# primary_LTC.net
KiCad netlist of a schematic drawn in Altium Designer
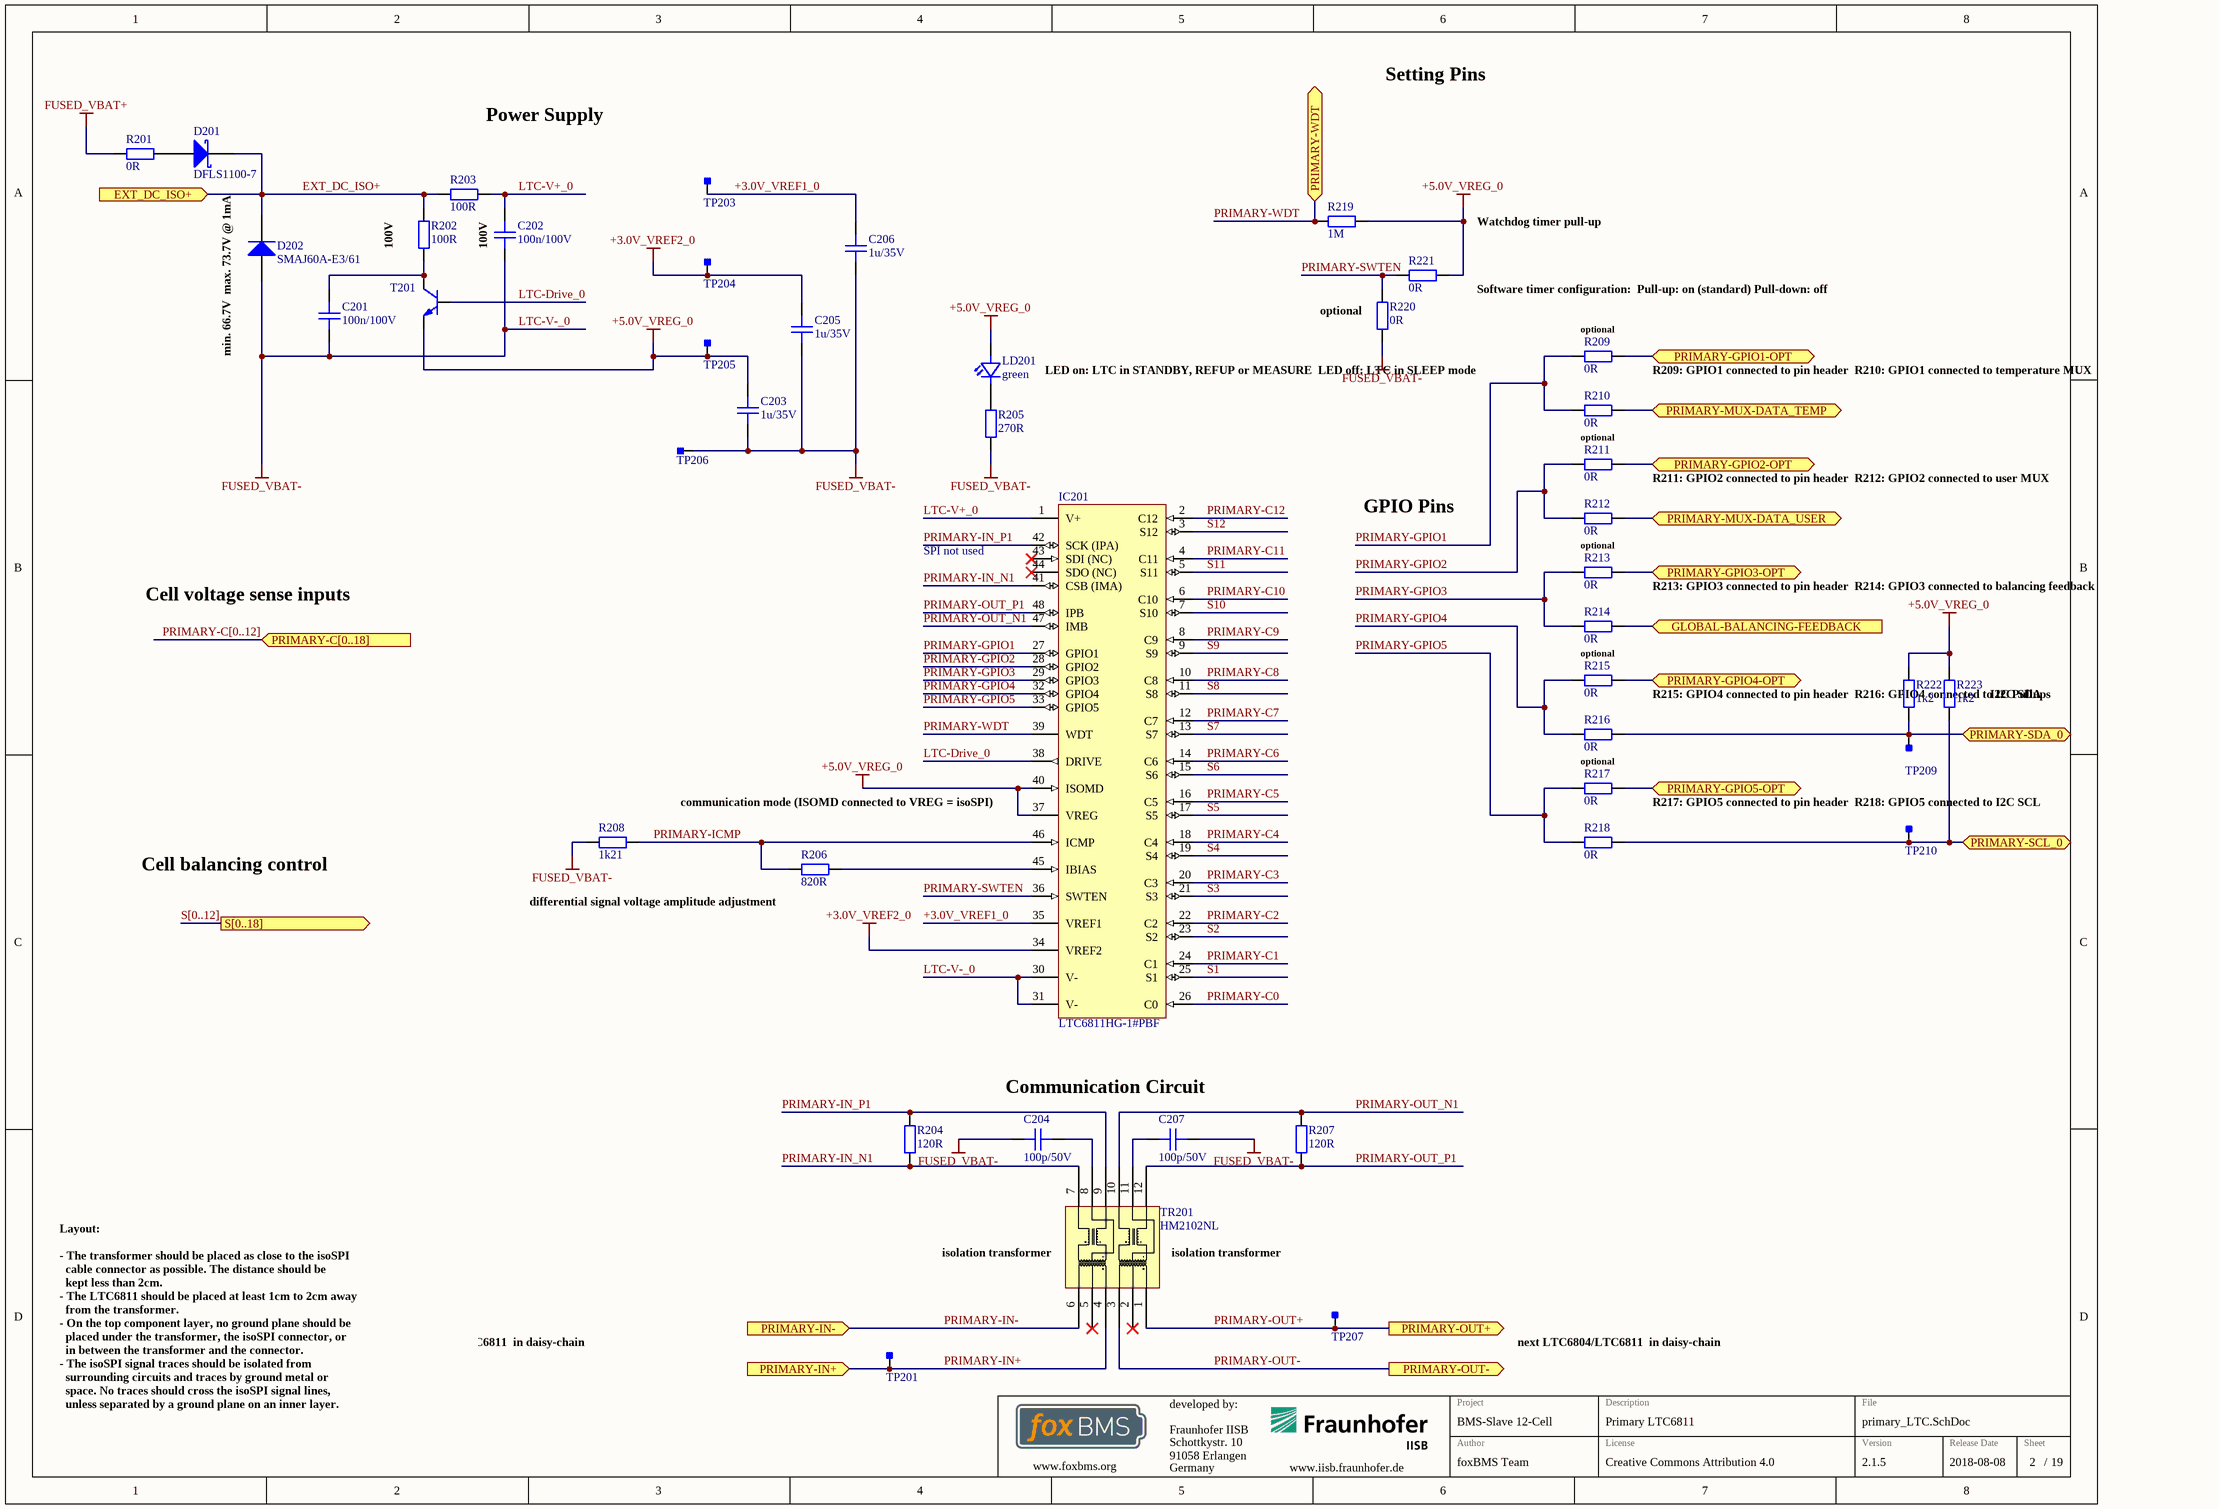
[diagram p0: primary_LTC.SchDoc]

(export (version "E")
  (design (tool "Eeschema 10.0.6"))
  (components
    (comp (ref "C201")
      (value "100n/100V")
      (footprint "CAPC2012X14N")
      (description "MLCC")
      (fields (field (name "PART NUMBER") "gen_C_ceramic_100n_100V_X7R_0805"))
      (libsource (lib "OE750") (part "C"))
    )
    (comp (ref "C202")
      (value "100n/100V")
      (footprint "CAPC2012X14N")
      (description "MLCC")
      (fields (field (name "PART NUMBER") "gen_C_ceramic_100n_100V_X7R_0805"))
      (libsource (lib "OE750") (part "C"))
    )
    (comp (ref "C203")
      (value "1u/35V")
      (footprint "CAPC1608X08N")
      (description "MLCC")
      (fields (field (name "PART NUMBER") "gen_C_ceramic_1u_35V_X7R_0603"))
      (libsource (lib "OE750") (part "C"))
    )
    (comp (ref "C204")
      (value "100p/50V")
      (footprint "CAPC1608X08N")
      (description "MLCC")
      (fields (field (name "PART NUMBER") "gen_C_ceramic_100p_50V_C0G_0603"))
      (libsource (lib "OE750") (part "C"))
    )
    (comp (ref "C205")
      (value "1u/35V")
      (footprint "CAPC1608X08N")
      (description "MLCC")
      (fields (field (name "PART NUMBER") "gen_C_ceramic_1u_35V_X7R_0603"))
      (libsource (lib "OE750") (part "C"))
    )
    (comp (ref "C206")
      (value "1u/35V")
      (footprint "CAPC1608X08N")
      (description "MLCC")
      (fields (field (name "PART NUMBER") "gen_C_ceramic_1u_35V_X7R_0603"))
      (libsource (lib "OE750") (part "C"))
    )
    (comp (ref "C207")
      (value "100p/50V")
      (footprint "CAPC1608X08N")
      (description "MLCC")
      (fields (field (name "PART NUMBER") "gen_C_ceramic_100p_50V_C0G_0603"))
      (libsource (lib "OE750") (part "C"))
    )
    (comp (ref "D201")
      (value "DFLS1100-7")
      (footprint "DIOD-POWERDI123-2_V")
      (fields (field (name "MANUFACTURER") "Diodes Inc"))
      (libsource (lib "Altium Content Vault") (part "DSKY-AK-2"))
    )
    (comp (ref "D202")
      (value "SMAJ60A-E3/61")
      (footprint "VISH-DO-214AC-2_N")
      (fields (field (name "MANUFACTURER") "Vishay Semiconductor"))
      (libsource (lib "Altium Content Vault") (part "VISH-K1A2-2"))
    )
    (comp (ref "IC201")
      (value "LTC6811HG-1#PBF")
      (footprint "LT-G-48_L")
      (description "Multicell Battery Monitor, 60 V Vin MAX, 48-pin SOP (G-48), -40 to 125 degC, Pb-Free")
      (fields (field (name "MANUFACTURER") "Linear Technology"))
      (libsource (lib "OE750") (part "LTC6811HG-1#PBF"))
    )
    (comp (ref "LD201")
      (value "green")
      (footprint "LEDC1608X07N")
      (description "LED")
      (fields (field (name "PART NUMBER") "gen_LED_0603_green"))
      (libsource (lib "OE750") (part "D_LED"))
    )
    (comp (ref "R201")
      (value "0R")
      (footprint "RESC2012X05N")
      (description "SMD Resistor 0R 0805")
      (fields (field (name "PART NUMBER") "gen_R_0R_0805") (field (name "POWER") "0.125W"))
      (libsource (lib "OE750") (part "R"))
    )
    (comp (ref "R202")
      (value "100R")
      (footprint "RESC2012X05N")
      (description "SMD Resistor 100R 0805")
      (fields (field (name "PART NUMBER") "gen_R_100R_0805") (field (name "TOLERANCE") "1%"))
      (libsource (lib "OE750") (part "R"))
    )
    (comp (ref "R203")
      (value "100R")
      (footprint "RESC2012X05N")
      (description "SMD Resistor 100R 0805")
      (fields (field (name "PART NUMBER") "gen_R_100R_0805") (field (name "TOLERANCE") "1%"))
      (libsource (lib "OE750") (part "R"))
    )
    (comp (ref "R204")
      (value "120R")
      (footprint "RESC1608X05N")
      (description "SMD Resistor 120R 0603")
      (fields (field (name "PART NUMBER") "gen_R_120R_0603") (field (name "TOLERANCE") "1%"))
      (libsource (lib "OE750") (part "R"))
    )
    (comp (ref "R205")
      (value "270R")
      (footprint "RESC1608X05N")
      (description "SMD Resistor 270R 0603")
      (fields (field (name "PART NUMBER") "gen_R_270R_0603") (field (name "TOLERANCE") "1%"))
      (libsource (lib "OE750") (part "R"))
    )
    (comp (ref "R206")
      (value "820R")
      (footprint "RESC1608X05N")
      (description "SMD Resistor 820R 0603")
      (fields (field (name "PART NUMBER") "gen_R_820R_0603") (field (name "TOLERANCE") "1%"))
      (libsource (lib "OE750") (part "R"))
    )
    (comp (ref "R207")
      (value "120R")
      (footprint "RESC1608X05N")
      (description "SMD Resistor 120R 0603")
      (fields (field (name "PART NUMBER") "gen_R_120R_0603") (field (name "TOLERANCE") "1%"))
      (libsource (lib "OE750") (part "R"))
    )
    (comp (ref "R208")
      (value "1k21")
      (footprint "RESC1608X05N")
      (description "SMD Resistor 1k21 0603")
      (fields (field (name "PART NUMBER") "gen_R_1k21_0603") (field (name "TOLERANCE") "1%"))
      (libsource (lib "OE750") (part "R"))
    )
    (comp (ref "R209")
      (value "0R")
      (footprint "RESC1608X05N")
      (description "SMD Resistor 0R 0603")
      (fields (field (name "PART NUMBER") "gen_R_0R_0603") (field (name "POWER") "0.1W"))
      (libsource (lib "OE750") (part "R"))
    )
    (comp (ref "R210")
      (value "0R")
      (footprint "RESC1608X05N")
      (description "SMD Resistor 0R 0603")
      (fields (field (name "PART NUMBER") "gen_R_0R_0603") (field (name "POWER") "0.1W"))
      (libsource (lib "OE750") (part "R"))
    )
    (comp (ref "R211")
      (value "0R")
      (footprint "RESC1608X05N")
      (description "SMD Resistor 0R 0603")
      (fields (field (name "PART NUMBER") "gen_R_0R_0603") (field (name "POWER") "0.1W"))
      (libsource (lib "OE750") (part "R"))
    )
    (comp (ref "R212")
      (value "0R")
      (footprint "RESC1608X05N")
      (description "SMD Resistor 0R 0603")
      (fields (field (name "PART NUMBER") "gen_R_0R_0603") (field (name "POWER") "0.1W"))
      (libsource (lib "OE750") (part "R"))
    )
    (comp (ref "R213")
      (value "0R")
      (footprint "RESC1608X05N")
      (description "SMD Resistor 0R 0603")
      (fields (field (name "PART NUMBER") "gen_R_0R_0603") (field (name "POWER") "0.1W"))
      (libsource (lib "OE750") (part "R"))
    )
    (comp (ref "R214")
      (value "0R")
      (footprint "RESC1608X05N")
      (description "SMD Resistor 0R 0603")
      (fields (field (name "PART NUMBER") "gen_R_0R_0603") (field (name "POWER") "0.1W"))
      (libsource (lib "OE750") (part "R"))
    )
    (comp (ref "R215")
      (value "0R")
      (footprint "RESC1608X05N")
      (description "SMD Resistor 0R 0603")
      (fields (field (name "PART NUMBER") "gen_R_0R_0603") (field (name "POWER") "0.1W"))
      (libsource (lib "OE750") (part "R"))
    )
    (comp (ref "R216")
      (value "0R")
      (footprint "RESC1608X05N")
      (description "SMD Resistor 0R 0603")
      (fields (field (name "PART NUMBER") "gen_R_0R_0603") (field (name "POWER") "0.1W"))
      (libsource (lib "OE750") (part "R"))
    )
    (comp (ref "R217")
      (value "0R")
      (footprint "RESC1608X05N")
      (description "SMD Resistor 0R 0603")
      (fields (field (name "PART NUMBER") "gen_R_0R_0603") (field (name "POWER") "0.1W"))
      (libsource (lib "OE750") (part "R"))
    )
    (comp (ref "R218")
      (value "0R")
      (footprint "RESC1608X05N")
      (description "SMD Resistor 0R 0603")
      (fields (field (name "PART NUMBER") "gen_R_0R_0603") (field (name "POWER") "0.1W"))
      (libsource (lib "OE750") (part "R"))
    )
    (comp (ref "R219")
      (value "1M")
      (footprint "RESC1608X05N")
      (description "SMD Resistor 1M 0603")
      (fields (field (name "PART NUMBER") "gen_R_1M_0603") (field (name "TOLERANCE") "1%"))
      (libsource (lib "OE750") (part "R"))
    )
    (comp (ref "R220")
      (value "0R")
      (footprint "RESC1608X05N")
      (description "SMD Resistor 0R 0603")
      (fields (field (name "PART NUMBER") "gen_R_0R_0603") (field (name "POWER") "0.1W"))
      (libsource (lib "OE750") (part "R"))
    )
    (comp (ref "R221")
      (value "0R")
      (footprint "RESC1608X05N")
      (description "SMD Resistor 0R 0603")
      (fields (field (name "PART NUMBER") "gen_R_0R_0603") (field (name "POWER") "0.1W"))
      (libsource (lib "OE750") (part "R"))
    )
    (comp (ref "R222")
      (value "1k2")
      (footprint "RESC1608X05N")
      (description "SMD Resistor 1k2 0603")
      (fields (field (name "PART NUMBER") "gen_R_1k2_0603") (field (name "TOLERANCE") "1%"))
      (libsource (lib "OE750") (part "R"))
    )
    (comp (ref "R223")
      (value "1k2")
      (footprint "RESC1608X05N")
      (description "SMD Resistor 1k2 0603")
      (fields (field (name "PART NUMBER") "gen_R_1k2_0603") (field (name "TOLERANCE") "1%"))
      (libsource (lib "OE750") (part "R"))
    )
    (comp (ref "T201")
      (value "PBHV8115Z")
      (footprint "SOT230P700X180-4N")
      (description "150 V, 1 A NPN high-voltage low V\r\nCEsat\r\n (BISS) transistor")
      (fields (field (name "MANUFACTURER") "Nexperia"))
      (libsource (lib "OE750") (part "NPN_4_PIN"))
    )
    (comp (ref "TP201")
      (value "Testpoint_Square")
      (footprint "Testpoint_S1")
      (description "Testpoint, square")
      (libsource (lib "OE750") (part "Testpoint_Square"))
    )
    (comp (ref "TP203")
      (value "Testpoint_Square")
      (footprint "Testpoint_S1")
      (description "Testpoint, square")
      (libsource (lib "OE750") (part "Testpoint_Square"))
    )
    (comp (ref "TP204")
      (value "Testpoint_Square")
      (footprint "Testpoint_S1")
      (description "Testpoint, square")
      (libsource (lib "OE750") (part "Testpoint_Square"))
    )
    (comp (ref "TP205")
      (value "Testpoint_Square")
      (footprint "Testpoint_S1")
      (description "Testpoint, square")
      (libsource (lib "OE750") (part "Testpoint_Square"))
    )
    (comp (ref "TP206")
      (value "Testpoint_Square")
      (footprint "Testpoint_S1")
      (description "Testpoint, square")
      (libsource (lib "OE750") (part "Testpoint_Square"))
    )
    (comp (ref "TP207")
      (value "Testpoint_Square")
      (footprint "Testpoint_S1")
      (description "Testpoint, square")
      (libsource (lib "OE750") (part "Testpoint_Square"))
    )
    (comp (ref "TP209")
      (value "Testpoint_Square")
      (footprint "Testpoint_S1")
      (description "Testpoint, square")
      (libsource (lib "OE750") (part "Testpoint_Square"))
    )
    (comp (ref "TP210")
      (value "Testpoint_Square")
      (footprint "Testpoint_S1")
      (description "Testpoint, square")
      (libsource (lib "OE750") (part "Testpoint_Square"))
    )
    (comp (ref "TR201")
      (value "HM2102NL")
      (footprint "HM2102NL")
      (description "Pulse HM2102NL BMS Transformer")
      (fields (field (name "MANUFACTURER") "Pulse"))
      (libsource (lib "OE750") (part "HM2102NL"))
    )
  )
  (nets
    (net (code "2") (name "+3.0V_VREF2_0") (class "Default")
      (node (ref "C205") (pin "2") (pinfunction "2_2") (pintype "passive"))
      (node (ref "IC201") (pin "34") (pinfunction "VREF2_34") (pintype "passive"))
      (node (ref "TP204") (pin "1") (pinfunction "1_1") (pintype "passive"))
    )
    (net (code "3") (name "+5.0V_VREG_0") (class "Default")
      (node (ref "C203") (pin "2") (pinfunction "2_2") (pintype "passive"))
      (node (ref "IC201") (pin "37") (pinfunction "VREG_37") (pintype "power_in"))
      (node (ref "IC201") (pin "40") (pinfunction "ISOMD_40") (pintype "input"))
      (node (ref "LD201") (pin "2") (pinfunction "A_2") (pintype "passive"))
      (node (ref "R219") (pin "2") (pinfunction "2_2") (pintype "passive"))
      (node (ref "R221") (pin "2") (pinfunction "2_2") (pintype "passive"))
      (node (ref "R222") (pin "2") (pinfunction "2_2") (pintype "passive"))
      (node (ref "R223") (pin "2") (pinfunction "2_2") (pintype "passive"))
      (node (ref "T201") (pin "3") (pinfunction "E_3") (pintype "passive"))
      (node (ref "TP205") (pin "1") (pinfunction "1_1") (pintype "passive"))
    )
    (net (code "4") (name "/+3.0V_VREF1_0") (class "Default")
      (node (ref "C206") (pin "2") (pinfunction "2_2") (pintype "passive"))
      (node (ref "IC201") (pin "35") (pinfunction "VREF1_35") (pintype "passive"))
      (node (ref "TP203") (pin "1") (pinfunction "1_1") (pintype "passive"))
    )
    (net (code "5") (name "/EXT_DC_ISO+") (class "Default")
      (node (ref "D201") (pin "2") (pinfunction "K_2") (pintype "passive"))
      (node (ref "D202") (pin "1") (pinfunction "K_1") (pintype "passive"))
      (node (ref "R202") (pin "2") (pinfunction "2_2") (pintype "passive"))
      (node (ref "R203") (pin "1") (pinfunction "1_1") (pintype "passive"))
    )
    (net (code "6") (name "/GLOBAL-BALANCING-FEEDBACK") (class "Default")
      (node (ref "R214") (pin "1") (pinfunction "1_1") (pintype "passive"))
    )
    (net (code "7") (name "/LTC-Drive_0") (class "Default")
      (node (ref "IC201") (pin "38") (pinfunction "DRIVE_38") (pintype "output"))
      (node (ref "T201") (pin "1") (pinfunction "B_1") (pintype "passive"))
    )
    (net (code "8") (name "/LTC-V+_0") (class "Default")
      (node (ref "C202") (pin "1") (pinfunction "1_1") (pintype "passive"))
      (node (ref "IC201") (pin "1") (pinfunction "V+_1") (pintype "power_in"))
      (node (ref "R203") (pin "2") (pinfunction "2_2") (pintype "passive"))
    )
    (net (code "9") (name "/PRIMARY-C0") (class "Default")
      (node (ref "IC201") (pin "26") (pinfunction "C0_26") (pintype "input"))
    )
    (net (code "10") (name "/PRIMARY-C1") (class "Default")
      (node (ref "IC201") (pin "24") (pinfunction "C1_24") (pintype "input"))
    )
    (net (code "11") (name "/PRIMARY-C2") (class "Default")
      (node (ref "IC201") (pin "22") (pinfunction "C2_22") (pintype "input"))
    )
    (net (code "12") (name "/PRIMARY-C3") (class "Default")
      (node (ref "IC201") (pin "20") (pinfunction "C3_20") (pintype "input"))
    )
    (net (code "13") (name "/PRIMARY-C4") (class "Default")
      (node (ref "IC201") (pin "18") (pinfunction "C4_18") (pintype "input"))
    )
    (net (code "14") (name "/PRIMARY-C5") (class "Default")
      (node (ref "IC201") (pin "16") (pinfunction "C5_16") (pintype "input"))
    )
    (net (code "15") (name "/PRIMARY-C6") (class "Default")
      (node (ref "IC201") (pin "14") (pinfunction "C6_14") (pintype "input"))
    )
    (net (code "16") (name "/PRIMARY-C7") (class "Default")
      (node (ref "IC201") (pin "12") (pinfunction "C7_12") (pintype "input"))
    )
    (net (code "17") (name "/PRIMARY-C8") (class "Default")
      (node (ref "IC201") (pin "10") (pinfunction "C8_10") (pintype "input"))
    )
    (net (code "18") (name "/PRIMARY-C9") (class "Default")
      (node (ref "IC201") (pin "8") (pinfunction "C9_8") (pintype "input"))
    )
    (net (code "19") (name "/PRIMARY-C10") (class "Default")
      (node (ref "IC201") (pin "6") (pinfunction "C10_6") (pintype "input"))
    )
    (net (code "20") (name "/PRIMARY-C11") (class "Default")
      (node (ref "IC201") (pin "4") (pinfunction "C11_4") (pintype "input"))
    )
    (net (code "21") (name "/PRIMARY-C12") (class "Default")
      (node (ref "IC201") (pin "2") (pinfunction "C12_2") (pintype "input"))
    )
    (net (code "23") (name "/PRIMARY-GPIO1") (class "Default")
      (node (ref "IC201") (pin "27") (pinfunction "GPIO1_27") (pintype "bidirectional"))
      (node (ref "R209") (pin "2") (pinfunction "2_2") (pintype "passive"))
      (node (ref "R210") (pin "2") (pinfunction "2_2") (pintype "passive"))
    )
    (net (code "24") (name "/PRIMARY-GPIO1-OPT") (class "Default")
      (node (ref "R209") (pin "1") (pinfunction "1_1") (pintype "passive"))
    )
    (net (code "25") (name "/PRIMARY-GPIO2") (class "Default")
      (node (ref "IC201") (pin "28") (pinfunction "GPIO2_28") (pintype "bidirectional"))
      (node (ref "R211") (pin "2") (pinfunction "2_2") (pintype "passive"))
      (node (ref "R212") (pin "2") (pinfunction "2_2") (pintype "passive"))
    )
    (net (code "26") (name "/PRIMARY-GPIO2-OPT") (class "Default")
      (node (ref "R211") (pin "1") (pinfunction "1_1") (pintype "passive"))
    )
    (net (code "27") (name "/PRIMARY-GPIO3") (class "Default")
      (node (ref "IC201") (pin "29") (pinfunction "GPIO3_29") (pintype "bidirectional"))
      (node (ref "R213") (pin "2") (pinfunction "2_2") (pintype "passive"))
      (node (ref "R214") (pin "2") (pinfunction "2_2") (pintype "passive"))
    )
    (net (code "28") (name "/PRIMARY-GPIO3-OPT") (class "Default")
      (node (ref "R213") (pin "1") (pinfunction "1_1") (pintype "passive"))
    )
    (net (code "29") (name "/PRIMARY-GPIO4") (class "Default")
      (node (ref "IC201") (pin "32") (pinfunction "GPIO4_32") (pintype "bidirectional"))
      (node (ref "R215") (pin "2") (pinfunction "2_2") (pintype "passive"))
      (node (ref "R216") (pin "2") (pinfunction "2_2") (pintype "passive"))
    )
    (net (code "30") (name "/PRIMARY-GPIO4-OPT") (class "Default")
      (node (ref "R215") (pin "1") (pinfunction "1_1") (pintype "passive"))
    )
    (net (code "31") (name "/PRIMARY-GPIO5") (class "Default")
      (node (ref "IC201") (pin "33") (pinfunction "GPIO5_33") (pintype "bidirectional"))
      (node (ref "R217") (pin "2") (pinfunction "2_2") (pintype "passive"))
      (node (ref "R218") (pin "2") (pinfunction "2_2") (pintype "passive"))
    )
    (net (code "32") (name "/PRIMARY-GPIO5-OPT") (class "Default")
      (node (ref "R217") (pin "1") (pinfunction "1_1") (pintype "passive"))
    )
    (net (code "33") (name "/PRIMARY-ICMP") (class "Default")
      (node (ref "IC201") (pin "46") (pinfunction "ICMP_46") (pintype "input"))
      (node (ref "R206") (pin "1") (pinfunction "1_1") (pintype "passive"))
      (node (ref "R208") (pin "2") (pinfunction "2_2") (pintype "passive"))
    )
    (net (code "34") (name "/PRIMARY-IN+") (class "Default")
      (node (ref "TP201") (pin "1") (pinfunction "1_1") (pintype "passive"))
      (node (ref "TR201") (pin "4") (pintype "passive"))
    )
    (net (code "35") (name "/PRIMARY-IN-") (class "Default")
      (node (ref "TR201") (pin "6") (pintype "passive"))
    )
    (net (code "36") (name "/PRIMARY-IN_N1") (class "Default")
      (node (ref "IC201") (pin "41") (pinfunction "CSB_(IMA)_41") (pintype "bidirectional"))
      (node (ref "R204") (pin "2") (pinfunction "2_2") (pintype "passive"))
      (node (ref "TR201") (pin "7") (pintype "passive"))
    )
    (net (code "37") (name "/PRIMARY-IN_P1") (class "Default")
      (node (ref "IC201") (pin "42") (pinfunction "SCK_(IPA)_42") (pintype "bidirectional"))
      (node (ref "R204") (pin "1") (pinfunction "1_1") (pintype "passive"))
      (node (ref "TR201") (pin "9") (pintype "passive"))
    )
    (net (code "38") (name "/PRIMARY-MUX-DATA_TEMP") (class "Default")
      (node (ref "R210") (pin "1") (pinfunction "1_1") (pintype "passive"))
    )
    (net (code "39") (name "/PRIMARY-MUX-DATA_USER") (class "Default")
      (node (ref "R212") (pin "1") (pinfunction "1_1") (pintype "passive"))
    )
    (net (code "40") (name "/PRIMARY-OUT+") (class "Default")
      (node (ref "TP207") (pin "1") (pinfunction "1_1") (pintype "passive"))
      (node (ref "TR201") (pin "1") (pintype "passive"))
    )
    (net (code "41") (name "/PRIMARY-OUT-") (class "Default")
      (node (ref "TR201") (pin "3") (pintype "passive"))
    )
    (net (code "42") (name "/PRIMARY-OUT_N1") (class "Default")
      (node (ref "IC201") (pin "47") (pinfunction "IMB_47") (pintype "bidirectional"))
      (node (ref "R207") (pin "2") (pinfunction "2_2") (pintype "passive"))
      (node (ref "TR201") (pin "10") (pintype "passive"))
    )
    (net (code "43") (name "/PRIMARY-OUT_P1") (class "Default")
      (node (ref "IC201") (pin "48") (pinfunction "IPB_48") (pintype "bidirectional"))
      (node (ref "R207") (pin "1") (pinfunction "1_1") (pintype "passive"))
      (node (ref "TR201") (pin "12") (pintype "passive"))
    )
    (net (code "44") (name "/PRIMARY-SCL_0") (class "Default")
      (node (ref "R218") (pin "1") (pinfunction "1_1") (pintype "passive"))
      (node (ref "R223") (pin "1") (pinfunction "1_1") (pintype "passive"))
      (node (ref "TP210") (pin "1") (pinfunction "1_1") (pintype "passive"))
    )
    (net (code "45") (name "/PRIMARY-SDA_0") (class "Default")
      (node (ref "R216") (pin "1") (pinfunction "1_1") (pintype "passive"))
      (node (ref "R222") (pin "1") (pinfunction "1_1") (pintype "passive"))
      (node (ref "TP209") (pin "1") (pinfunction "1_1") (pintype "passive"))
    )
    (net (code "46") (name "/PRIMARY-SWTEN") (class "Default")
      (node (ref "IC201") (pin "36") (pinfunction "SWTEN_36") (pintype "input"))
      (node (ref "R220") (pin "2") (pinfunction "2_2") (pintype "passive"))
      (node (ref "R221") (pin "1") (pinfunction "1_1") (pintype "passive"))
    )
    (net (code "47") (name "/PRIMARY-WDT") (class "Default")
      (node (ref "IC201") (pin "39") (pinfunction "WDT_39") (pintype "tri_state"))
      (node (ref "R219") (pin "1") (pinfunction "1_1") (pintype "passive"))
    )
    (net (code "48") (name "/S1") (class "Default")
      (node (ref "IC201") (pin "25") (pinfunction "S1_25") (pintype "bidirectional"))
    )
    (net (code "49") (name "/S2") (class "Default")
      (node (ref "IC201") (pin "23") (pinfunction "S2_23") (pintype "bidirectional"))
    )
    (net (code "50") (name "/S3") (class "Default")
      (node (ref "IC201") (pin "21") (pinfunction "S3_21") (pintype "bidirectional"))
    )
    (net (code "51") (name "/S4") (class "Default")
      (node (ref "IC201") (pin "19") (pinfunction "S4_19") (pintype "bidirectional"))
    )
    (net (code "52") (name "/S5") (class "Default")
      (node (ref "IC201") (pin "17") (pinfunction "S5_17") (pintype "bidirectional"))
    )
    (net (code "53") (name "/S6") (class "Default")
      (node (ref "IC201") (pin "15") (pinfunction "S6_15") (pintype "bidirectional"))
    )
    (net (code "54") (name "/S7") (class "Default")
      (node (ref "IC201") (pin "13") (pinfunction "S7_13") (pintype "bidirectional"))
    )
    (net (code "55") (name "/S8") (class "Default")
      (node (ref "IC201") (pin "11") (pinfunction "S8_11") (pintype "bidirectional"))
    )
    (net (code "56") (name "/S9") (class "Default")
      (node (ref "IC201") (pin "9") (pinfunction "S9_9") (pintype "bidirectional"))
    )
    (net (code "57") (name "/S10") (class "Default")
      (node (ref "IC201") (pin "7") (pinfunction "S10_7") (pintype "bidirectional"))
    )
    (net (code "58") (name "/S11") (class "Default")
      (node (ref "IC201") (pin "5") (pinfunction "S11_5") (pintype "bidirectional"))
    )
    (net (code "59") (name "/S12") (class "Default")
      (node (ref "IC201") (pin "3") (pinfunction "S12_3") (pintype "bidirectional"))
    )
    (net (code "61") (name "FUSED_VBAT+") (class "Default")
      (node (ref "R201") (pin "1") (pinfunction "1_1") (pintype "passive"))
    )
    (net (code "62") (name "FUSED_VBAT-") (class "Default")
      (node (ref "C201") (pin "2") (pinfunction "2_2") (pintype "passive"))
      (node (ref "C202") (pin "2") (pinfunction "2_2") (pintype "passive"))
      (node (ref "C203") (pin "1") (pinfunction "1_1") (pintype "passive"))
      (node (ref "C204") (pin "1") (pinfunction "1_1") (pintype "passive"))
      (node (ref "C205") (pin "1") (pinfunction "1_1") (pintype "passive"))
      (node (ref "C206") (pin "1") (pinfunction "1_1") (pintype "passive"))
      (node (ref "C207") (pin "1") (pinfunction "1_1") (pintype "passive"))
      (node (ref "D202") (pin "2") (pinfunction "A_2") (pintype "passive"))
      (node (ref "IC201") (pin "30") (pinfunction "V-_30") (pintype "power_in"))
      (node (ref "IC201") (pin "31") (pinfunction "V-_31") (pintype "power_in"))
      (node (ref "R205") (pin "1") (pinfunction "1_1") (pintype "passive"))
      (node (ref "R208") (pin "1") (pinfunction "1_1") (pintype "passive"))
      (node (ref "R220") (pin "1") (pinfunction "1_1") (pintype "passive"))
      (node (ref "TP206") (pin "1") (pinfunction "1_1") (pintype "passive"))
    )
    (net (code "63") (name "Net-(C201-Pad1)") (class "Default")
      (node (ref "C201") (pin "1") (pinfunction "1_1") (pintype "passive"))
      (node (ref "R202") (pin "1") (pinfunction "1_1") (pintype "passive"))
      (node (ref "T201") (pin "2") (pinfunction "C_2") (pintype "passive"))
      (node (ref "T201") (pin "4") (pinfunction "C_4") (pintype "passive"))
    )
    (net (code "64") (name "Net-(C204-Pad2)") (class "Default")
      (node (ref "C204") (pin "2") (pinfunction "2_2") (pintype "passive"))
      (node (ref "TR201") (pin "8") (pintype "passive"))
    )
    (net (code "65") (name "Net-(C207-Pad2)") (class "Default")
      (node (ref "C207") (pin "2") (pinfunction "2_2") (pintype "passive"))
      (node (ref "TR201") (pin "11") (pintype "passive"))
    )
    (net (code "66") (name "Net-(D201-A)") (class "Default")
      (node (ref "D201") (pin "1") (pinfunction "A_1") (pintype "passive"))
      (node (ref "R201") (pin "2") (pinfunction "2_2") (pintype "passive"))
    )
    (net (code "67") (name "Net-(IC201-IBIAS)") (class "Default")
      (node (ref "IC201") (pin "45") (pinfunction "IBIAS_45") (pintype "input"))
      (node (ref "R206") (pin "2") (pinfunction "2_2") (pintype "passive"))
    )
    (net (code "68") (name "Net-(LD201-C)") (class "Default")
      (node (ref "LD201") (pin "1") (pinfunction "C_1") (pintype "passive"))
      (node (ref "R205") (pin "2") (pinfunction "2_2") (pintype "passive"))
    )
    (net (code "69") (name "unconnected-(IC201-SDI_(NC)-Pad43)") (class "Default")
      (node (ref "IC201") (pin "43") (pinfunction "SDI_(NC)_43") (pintype "input+no_connect"))
    )
    (net (code "70") (name "unconnected-(IC201-SDO_(NC)-Pad44)") (class "Default")
      (node (ref "IC201") (pin "44") (pinfunction "SDO_(NC)_44") (pintype "open_collector+no_connect"))
    )
    (net (code "71") (name "unconnected-(TR201-Pad2)") (class "Default")
      (node (ref "TR201") (pin "2") (pintype "passive+no_connect"))
    )
    (net (code "72") (name "unconnected-(TR201-Pad5)") (class "Default")
      (node (ref "TR201") (pin "5") (pintype "passive+no_connect"))
    )
  )
)
